# MSMGDustSensor.net
KiCad netlist of a schematic drawn in EAGLE
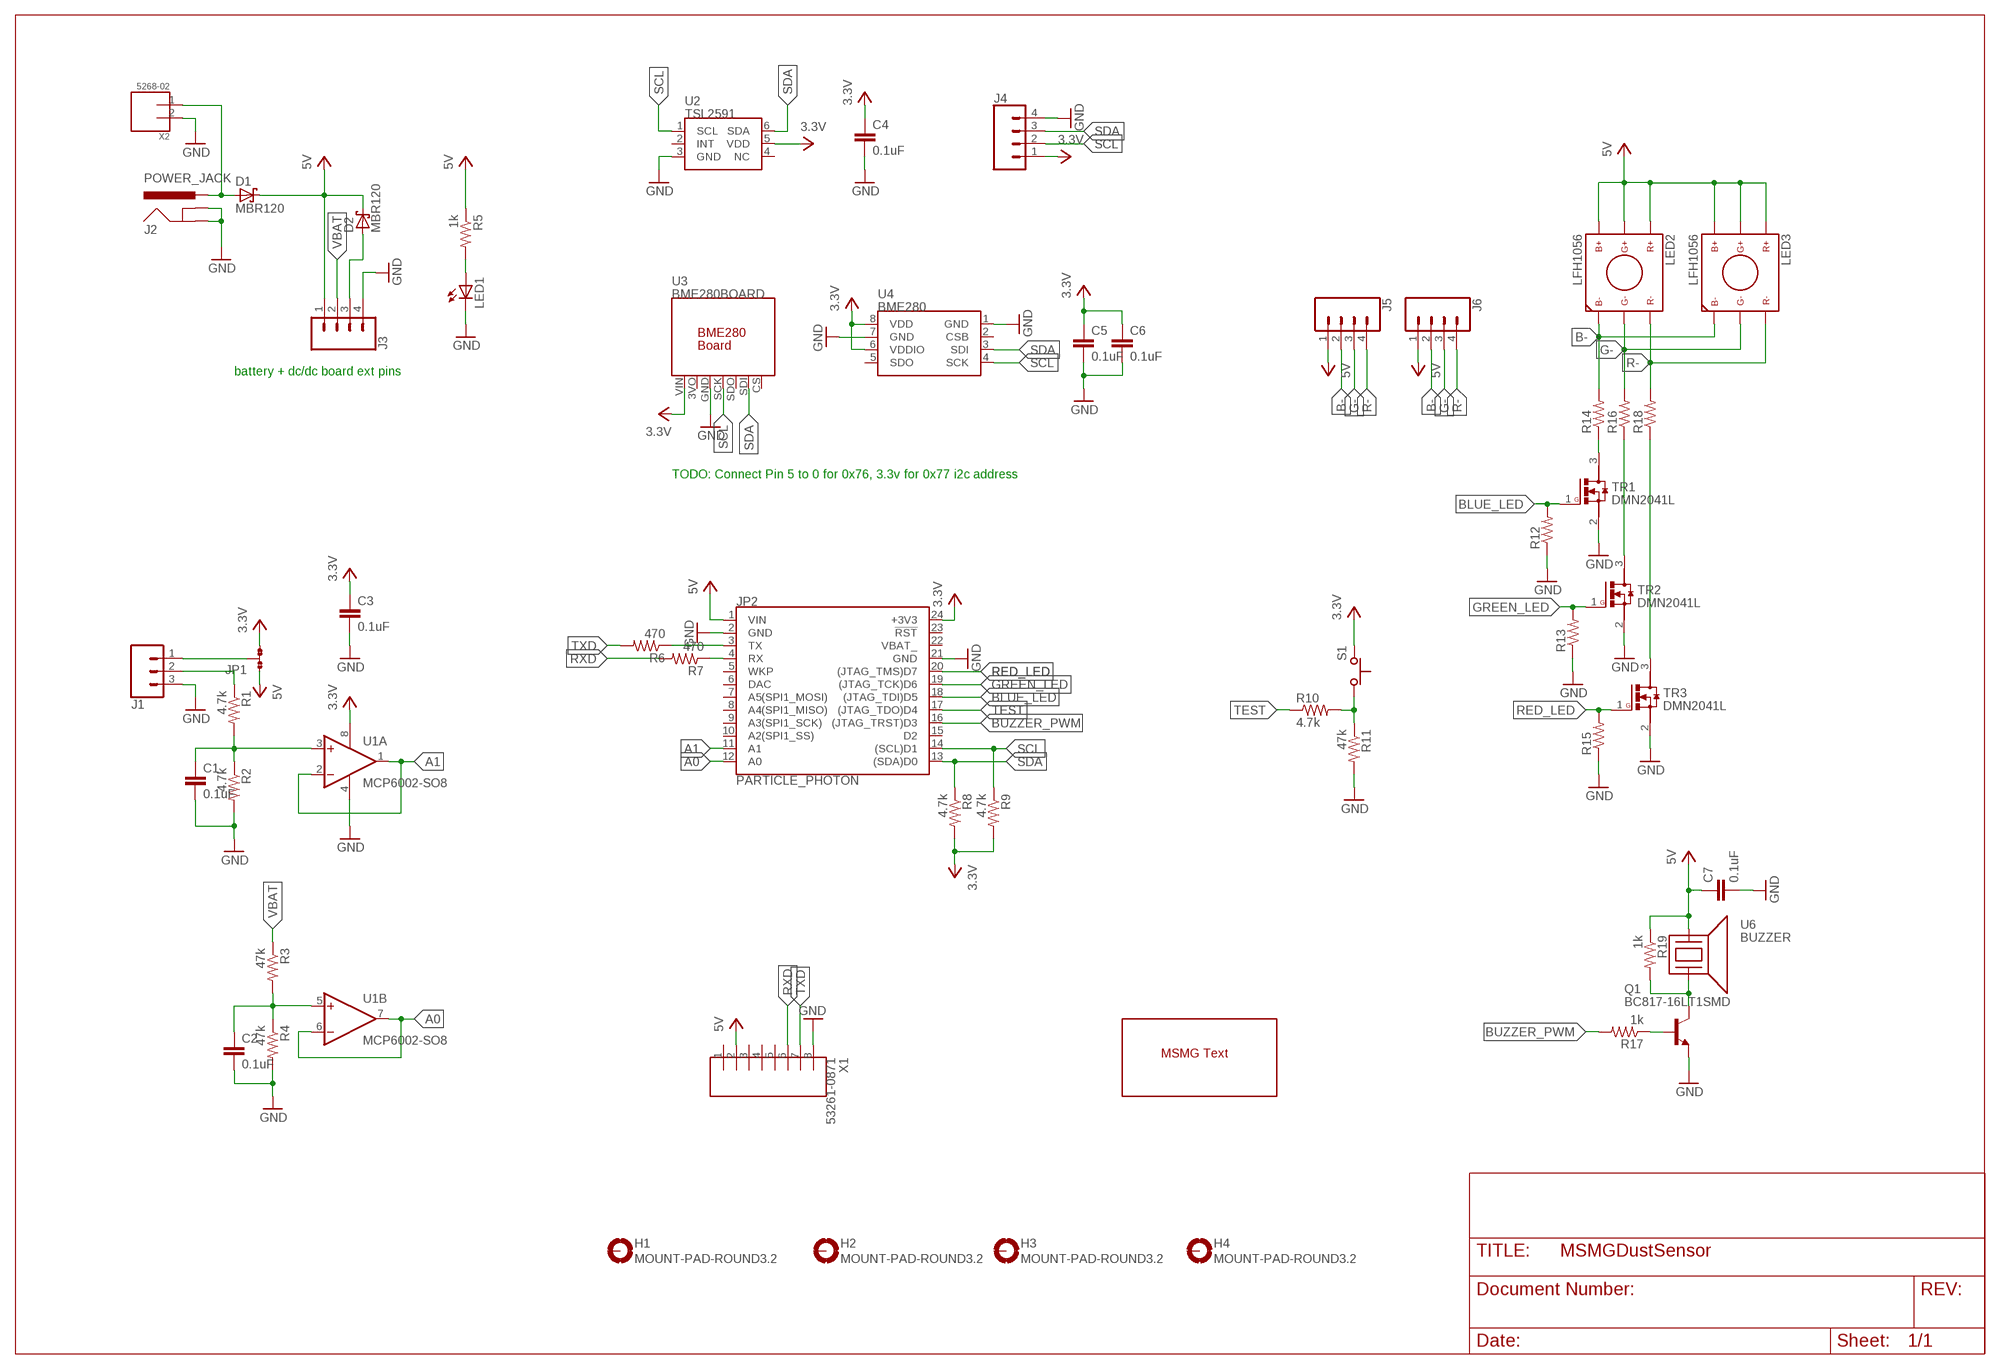
[diagram p0: schematic, sheet 1]

(export (version "E")
  (design (tool "Eeschema 10.0.6"))
  (components
    (comp (ref "C1")
      (value "0.1uF")
      (footprint "eagle-import:C0603(1608)")
      (libsource (lib "eagle-import") (part "C0603(1608)"))
    )
    (comp (ref "C2")
      (value "0.1uF")
      (footprint "eagle-import:C0603(1608)")
      (libsource (lib "eagle-import") (part "C0603(1608)"))
    )
    (comp (ref "C3")
      (value "0.1uF")
      (footprint "eagle-import:C0603(1608)")
      (libsource (lib "eagle-import") (part "C0603(1608)"))
    )
    (comp (ref "C4")
      (value "0.1uF")
      (footprint "eagle-import:C0603(1608)")
      (libsource (lib "eagle-import") (part "C0603(1608)"))
    )
    (comp (ref "C5")
      (value "0.1uF")
      (footprint "eagle-import:C0603(1608)")
      (libsource (lib "eagle-import") (part "C0603(1608)"))
    )
    (comp (ref "C6")
      (value "0.1uF")
      (footprint "eagle-import:C0603(1608)")
      (libsource (lib "eagle-import") (part "C0603(1608)"))
    )
    (comp (ref "C7")
      (value "0.1uF")
      (footprint "eagle-import:C0603(1608)")
      (libsource (lib "eagle-import") (part "C0603(1608)"))
    )
    (comp (ref "D1")
      (value "MBR120")
      (footprint "eagle-import:SOD-123")
      (libsource (lib "eagle-import") (part "MBR120"))
    )
    (comp (ref "D2")
      (value "MBR120")
      (footprint "eagle-import:SOD-123")
      (libsource (lib "eagle-import") (part "MBR120"))
    )
    (comp (ref "H1")
      (value "MOUNT-PAD-ROUND3.2")
      (footprint "eagle-import:3,2-PAD")
      (libsource (lib "eagle-import") (part "MOUNT-PAD-ROUND3.2"))
    )
    (comp (ref "H2")
      (value "MOUNT-PAD-ROUND3.2")
      (footprint "eagle-import:3,2-PAD")
      (libsource (lib "eagle-import") (part "MOUNT-PAD-ROUND3.2"))
    )
    (comp (ref "H3")
      (value "MOUNT-PAD-ROUND3.2")
      (footprint "eagle-import:3,2-PAD")
      (libsource (lib "eagle-import") (part "MOUNT-PAD-ROUND3.2"))
    )
    (comp (ref "H4")
      (value "MOUNT-PAD-ROUND3.2")
      (footprint "eagle-import:3,2-PAD")
      (libsource (lib "eagle-import") (part "MOUNT-PAD-ROUND3.2"))
    )
    (comp (ref "J1")
      (value "CONN_03")
      (footprint "eagle-import:1X03")
      (libsource (lib "eagle-import") (part "CONN_03"))
    )
    (comp (ref "J2")
      (value "POWER_JACK")
      (footprint "eagle-import:POWER_JACK_PTH")
      (libsource (lib "eagle-import") (part "POWER_JACK"))
    )
    (comp (ref "J3")
      (value "CONN_04")
      (footprint "eagle-import:1X04")
      (libsource (lib "eagle-import") (part "CONN_04"))
    )
    (comp (ref "J4")
      (value "CONN_04")
      (footprint "eagle-import:1X04")
      (libsource (lib "eagle-import") (part "CONN_04"))
    )
    (comp (ref "J5")
      (value "CONN_04")
      (footprint "eagle-import:1X04")
      (libsource (lib "eagle-import") (part "CONN_04"))
    )
    (comp (ref "J6")
      (value "CONN_04")
      (footprint "eagle-import:1X04")
      (libsource (lib "eagle-import") (part "CONN_04"))
    )
    (comp (ref "JP1")
      (value "JP2")
      (footprint "eagle-import:JP2SMD0603")
      (libsource (lib "eagle-import") (part "JP2"))
    )
    (comp (ref "JP2")
      (value "PARTICLE_PHOTON")
      (footprint "eagle-import:PARTICLE_PHOTON")
      (libsource (lib "eagle-import") (part "PARTICLE_PHOTON"))
    )
    (comp (ref "LED1")
      (value "LED3MM")
      (footprint "eagle-import:LED3MM")
      (libsource (lib "eagle-import") (part "LED3MM"))
    )
    (comp (ref "LED2")
      (value "LFH1056")
      (footprint "eagle-import:LFH1056")
      (libsource (lib "eagle-import") (part "LFH1056"))
    )
    (comp (ref "LED3")
      (value "LFH1056")
      (footprint "eagle-import:LFH1056")
      (libsource (lib "eagle-import") (part "LFH1056"))
    )
    (comp (ref "Q1")
      (value "BC817-16LT1SMD")
      (footprint "eagle-import:SOT23-BEC")
      (libsource (lib "eagle-import") (part "BC817SMD-16LT1"))
    )
    (comp (ref "R1")
      (value "4.7k")
      (footprint "eagle-import:R0603(1608)")
      (libsource (lib "eagle-import") (part "R0603(1608)"))
    )
    (comp (ref "R2")
      (value "4.7k")
      (footprint "eagle-import:R0603(1608)")
      (libsource (lib "eagle-import") (part "R0603(1608)"))
    )
    (comp (ref "R3")
      (value "47k")
      (footprint "eagle-import:R0603(1608)")
      (libsource (lib "eagle-import") (part "R0603(1608)"))
    )
    (comp (ref "R4")
      (value "47k")
      (footprint "eagle-import:R0603(1608)")
      (libsource (lib "eagle-import") (part "R0603(1608)"))
    )
    (comp (ref "R5")
      (value "1k")
      (footprint "eagle-import:R0603(1608)")
      (libsource (lib "eagle-import") (part "R0603(1608)"))
    )
    (comp (ref "R6")
      (value "470")
      (footprint "eagle-import:R0603(1608)")
      (libsource (lib "eagle-import") (part "R0603(1608)"))
    )
    (comp (ref "R7")
      (value "470")
      (footprint "eagle-import:R0603(1608)")
      (libsource (lib "eagle-import") (part "R0603(1608)"))
    )
    (comp (ref "R8")
      (value "4.7k")
      (footprint "eagle-import:R0603(1608)")
      (libsource (lib "eagle-import") (part "R0603(1608)"))
    )
    (comp (ref "R9")
      (value "4.7k")
      (footprint "eagle-import:R0603(1608)")
      (libsource (lib "eagle-import") (part "R0603(1608)"))
    )
    (comp (ref "R10")
      (value "4.7k")
      (footprint "eagle-import:R0603(1608)")
      (libsource (lib "eagle-import") (part "R0603(1608)"))
    )
    (comp (ref "R11")
      (value "47k")
      (footprint "eagle-import:R0603(1608)")
      (libsource (lib "eagle-import") (part "R0603(1608)"))
    )
    (comp (ref "R12")
      (value "R0603(1608)")
      (footprint "eagle-import:R0603(1608)")
      (libsource (lib "eagle-import") (part "R0603(1608)"))
    )
    (comp (ref "R13")
      (value "R0603(1608)")
      (footprint "eagle-import:R0603(1608)")
      (libsource (lib "eagle-import") (part "R0603(1608)"))
    )
    (comp (ref "R14")
      (value "R0603(1608)")
      (footprint "eagle-import:R0603(1608)")
      (libsource (lib "eagle-import") (part "R0603(1608)"))
    )
    (comp (ref "R15")
      (value "R0603(1608)")
      (footprint "eagle-import:R0603(1608)")
      (libsource (lib "eagle-import") (part "R0603(1608)"))
    )
    (comp (ref "R16")
      (value "R0603(1608)")
      (footprint "eagle-import:R0603(1608)")
      (libsource (lib "eagle-import") (part "R0603(1608)"))
    )
    (comp (ref "R17")
      (value "1k")
      (footprint "eagle-import:R0603(1608)")
      (libsource (lib "eagle-import") (part "R0603(1608)"))
    )
    (comp (ref "R18")
      (value "R0603(1608)")
      (footprint "eagle-import:R0603(1608)")
      (libsource (lib "eagle-import") (part "R0603(1608)"))
    )
    (comp (ref "R19")
      (value "1k")
      (footprint "eagle-import:R0603(1608)")
      (libsource (lib "eagle-import") (part "R0603(1608)"))
    )
    (comp (ref "S1")
      (value "SWITCH")
      (footprint "eagle-import:SKHLACA010")
      (libsource (lib "eagle-import") (part "SWITCH"))
    )
    (comp (ref "TR1")
      (value "DMN2041L")
      (footprint "eagle-import:SOT23")
      (libsource (lib "eagle-import") (part "DMN2041L"))
    )
    (comp (ref "TR2")
      (value "DMN2041L")
      (footprint "eagle-import:SOT23")
      (libsource (lib "eagle-import") (part "DMN2041L"))
    )
    (comp (ref "TR3")
      (value "DMN2041L")
      (footprint "eagle-import:SOT23")
      (libsource (lib "eagle-import") (part "DMN2041L"))
    )
    (comp (ref "U$1")
      (value "MSMG_TEXT")
      (footprint "eagle-import:MSMG_TEXT")
      (libsource (lib "eagle-import") (part "MSMG_TEXT"))
    )
    (comp (ref "U1")
      (value "MCP6002-SO8")
      (footprint "eagle-import:SO8")
      (libsource (lib "eagle-import") (part "MCP6002-SO8"))
    )
    (comp (ref "U2")
      (value "TSL2591")
      (footprint "eagle-import:DFN-6")
      (libsource (lib "eagle-import") (part "TSL2591"))
    )
    (comp (ref "U3")
      (value "BME280BOARD")
      (footprint "eagle-import:BME280BOARD")
      (libsource (lib "eagle-import") (part "BME280BOARD"))
    )
    (comp (ref "U4")
      (value "BME280")
      (footprint "eagle-import:BME280")
      (libsource (lib "eagle-import") (part "BME280"))
    )
    (comp (ref "U6")
      (value "BUZZER")
      (footprint "eagle-import:PS1240")
      (libsource (lib "eagle-import") (part "BUZZER"))
    )
    (comp (ref "X1")
      (value "53261-0871")
      (footprint "eagle-import:53261-0871")
      (libsource (lib "eagle-import") (part "53261-0871"))
    )
    (comp (ref "X2")
      (value "5268-02")
      (footprint "eagle-import:5628-02")
      (libsource (lib "eagle-import") (part "5268-02"))
    )
  )
  (nets
    (net (code "1") (name "/VBAT_") (class "Default")
      (node (ref "JP2") (pin "22") (pinfunction "VBAT__22") (pintype "power_in"))
    )
    (net (code "2") (name "3.3V") (class "Default")
      (node (ref "C3") (pin "1") (pinfunction "1_1") (pintype "passive"))
      (node (ref "C4") (pin "1") (pinfunction "1_1") (pintype "passive"))
      (node (ref "C5") (pin "1") (pinfunction "1_1") (pintype "passive"))
      (node (ref "C6") (pin "1") (pinfunction "1_1") (pintype "passive"))
      (node (ref "J4") (pin "1") (pinfunction "1_1") (pintype "passive"))
      (node (ref "JP1") (pin "3") (pinfunction "3_3") (pintype "passive"))
      (node (ref "JP2") (pin "24") (pinfunction "+3V3_24") (pintype "power_in"))
      (node (ref "R8") (pin "2") (pinfunction "2_2") (pintype "passive"))
      (node (ref "R9") (pin "2") (pinfunction "2_2") (pintype "passive"))
      (node (ref "S1") (pin "P$1") (pinfunction "P$1_P$1") (pintype "bidirectional"))
      (node (ref "U1") (pin "8") (pinfunction "V+_8") (pintype "power_in"))
      (node (ref "U2") (pin "5") (pinfunction "VDD_5") (pintype "bidirectional"))
      (node (ref "U3") (pin "VIN") (pinfunction "VIN_VIN") (pintype "bidirectional"))
      (node (ref "U4") (pin "6") (pinfunction "VDDIO_6") (pintype "power_in"))
      (node (ref "U4") (pin "8") (pinfunction "VDD_8") (pintype "power_in"))
    )
    (net (code "3") (name "5V") (class "Default")
      (node (ref "C7") (pin "1") (pinfunction "1_1") (pintype "passive"))
      (node (ref "D1") (pin "C") (pinfunction "C_C") (pintype "passive"))
      (node (ref "D2") (pin "C") (pinfunction "C_C") (pintype "passive"))
      (node (ref "J3") (pin "1") (pinfunction "1_1") (pintype "passive"))
      (node (ref "J5") (pin "1") (pinfunction "1_1") (pintype "passive"))
      (node (ref "J6") (pin "1") (pinfunction "1_1") (pintype "passive"))
      (node (ref "JP1") (pin "1") (pinfunction "1_1") (pintype "passive"))
      (node (ref "JP2") (pin "1") (pinfunction "VIN_1") (pintype "power_in"))
      (node (ref "LED2") (pin "B+") (pinfunction "B+_B+") (pintype "input"))
      (node (ref "LED2") (pin "G+") (pinfunction "G+_G+") (pintype "input"))
      (node (ref "LED2") (pin "R+") (pinfunction "R+_R+") (pintype "input"))
      (node (ref "LED3") (pin "B+") (pinfunction "B+_B+") (pintype "input"))
      (node (ref "LED3") (pin "G+") (pinfunction "G+_G+") (pintype "input"))
      (node (ref "LED3") (pin "R+") (pinfunction "R+_R+") (pintype "input"))
      (node (ref "R19") (pin "1") (pinfunction "1_1") (pintype "passive"))
      (node (ref "R5") (pin "1") (pinfunction "1_1") (pintype "passive"))
      (node (ref "U6") (pin "1") (pinfunction "P$1_1") (pintype "bidirectional"))
      (node (ref "X1") (pin "2") (pinfunction "2_2") (pintype "bidirectional"))
    )
    (net (code "4") (name "A0") (class "Default")
      (node (ref "JP2") (pin "12") (pinfunction "A0_12") (pintype "bidirectional"))
      (node (ref "U1") (pin "6") (pinfunction "-IN_6") (pintype "input"))
      (node (ref "U1") (pin "7") (pinfunction "OUT_7") (pintype "output"))
    )
    (net (code "5") (name "A1") (class "Default")
      (node (ref "JP2") (pin "11") (pinfunction "A1_11") (pintype "bidirectional"))
      (node (ref "U1") (pin "1") (pinfunction "OUT_1") (pintype "output"))
      (node (ref "U1") (pin "2") (pinfunction "-IN_2") (pintype "input"))
    )
    (net (code "6") (name "B-") (class "Default")
      (node (ref "J5") (pin "2") (pinfunction "2_2") (pintype "passive"))
      (node (ref "J6") (pin "2") (pinfunction "2_2") (pintype "passive"))
      (node (ref "LED2") (pin "B-") (pinfunction "B-_B-") (pintype "input"))
      (node (ref "LED3") (pin "B-") (pinfunction "B-_B-") (pintype "input"))
      (node (ref "R14") (pin "2") (pinfunction "2_2") (pintype "passive"))
    )
    (net (code "7") (name "BLUE_LED") (class "Default")
      (node (ref "JP2") (pin "18") (pinfunction "(JTAG_TDI)D5_18") (pintype "bidirectional"))
      (node (ref "R12") (pin "2") (pinfunction "2_2") (pintype "passive"))
      (node (ref "TR1") (pin "1") (pinfunction "G_1") (pintype "bidirectional"))
    )
    (net (code "8") (name "BUZZER_PWM") (class "Default")
      (node (ref "JP2") (pin "16") (pinfunction "(JTAG_TRST)D3_16") (pintype "bidirectional"))
      (node (ref "R17") (pin "2") (pinfunction "2_2") (pintype "passive"))
    )
    (net (code "9") (name "G-") (class "Default")
      (node (ref "J5") (pin "3") (pinfunction "3_3") (pintype "passive"))
      (node (ref "J6") (pin "3") (pinfunction "3_3") (pintype "passive"))
      (node (ref "LED2") (pin "G-") (pinfunction "G-_G-") (pintype "input"))
      (node (ref "LED3") (pin "G-") (pinfunction "G-_G-") (pintype "input"))
      (node (ref "R16") (pin "2") (pinfunction "2_2") (pintype "passive"))
    )
    (net (code "10") (name "GND") (class "Default")
      (node (ref "C1") (pin "2") (pinfunction "2_2") (pintype "passive"))
      (node (ref "C2") (pin "2") (pinfunction "2_2") (pintype "passive"))
      (node (ref "C3") (pin "2") (pinfunction "2_2") (pintype "passive"))
      (node (ref "C4") (pin "2") (pinfunction "2_2") (pintype "passive"))
      (node (ref "C5") (pin "2") (pinfunction "2_2") (pintype "passive"))
      (node (ref "C6") (pin "2") (pinfunction "2_2") (pintype "passive"))
      (node (ref "C7") (pin "2") (pinfunction "2_2") (pintype "passive"))
      (node (ref "J1") (pin "3") (pinfunction "3_3") (pintype "passive"))
      (node (ref "J2") (pin "GND") (pinfunction "GND_GND") (pintype "bidirectional"))
      (node (ref "J2") (pin "GNDBREAK") (pinfunction "GNDBREAK_GNDBREAK") (pintype "bidirectional"))
      (node (ref "J3") (pin "4") (pinfunction "4_4") (pintype "passive"))
      (node (ref "J4") (pin "4") (pinfunction "4_4") (pintype "passive"))
      (node (ref "JP2") (pin "2") (pinfunction "GND_2") (pintype "power_in"))
      (node (ref "JP2") (pin "21") (pinfunction "GND_21") (pintype "power_in"))
      (node (ref "LED1") (pin "K") (pinfunction "C_K") (pintype "passive"))
      (node (ref "Q1") (pin "E") (pinfunction "E_E") (pintype "passive"))
      (node (ref "R11") (pin "2") (pinfunction "2_2") (pintype "passive"))
      (node (ref "R12") (pin "1") (pinfunction "1_1") (pintype "passive"))
      (node (ref "R13") (pin "1") (pinfunction "1_1") (pintype "passive"))
      (node (ref "R15") (pin "1") (pinfunction "1_1") (pintype "passive"))
      (node (ref "R2") (pin "2") (pinfunction "2_2") (pintype "passive"))
      (node (ref "R4") (pin "2") (pinfunction "2_2") (pintype "passive"))
      (node (ref "TR1") (pin "2") (pinfunction "S_2") (pintype "bidirectional"))
      (node (ref "TR2") (pin "2") (pinfunction "S_2") (pintype "bidirectional"))
      (node (ref "TR3") (pin "2") (pinfunction "S_2") (pintype "bidirectional"))
      (node (ref "U1") (pin "4") (pinfunction "V-_4") (pintype "power_in"))
      (node (ref "U2") (pin "3") (pinfunction "GND_3") (pintype "bidirectional"))
      (node (ref "U3") (pin "GND") (pinfunction "GND_GND") (pintype "bidirectional"))
      (node (ref "U4") (pin "1") (pinfunction "GND_1") (pintype "power_in"))
      (node (ref "U4") (pin "7") (pinfunction "GND_7") (pintype "power_in"))
      (node (ref "X1") (pin "8") (pinfunction "8_8") (pintype "bidirectional"))
      (node (ref "X2") (pin "2") (pinfunction "2_2") (pintype "bidirectional"))
    )
    (net (code "11") (name "GREEN_LED") (class "Default")
      (node (ref "JP2") (pin "19") (pinfunction "(JTAG_TCK)D6_19") (pintype "bidirectional"))
      (node (ref "R13") (pin "2") (pinfunction "2_2") (pintype "passive"))
      (node (ref "TR2") (pin "1") (pinfunction "G_1") (pintype "bidirectional"))
    )
    (net (code "12") (name "Net-(D1-PadA)") (class "Default")
      (node (ref "D1") (pin "A") (pinfunction "A_A") (pintype "passive"))
      (node (ref "J2") (pin "PWR") (pinfunction "PWR_PWR") (pintype "bidirectional"))
      (node (ref "X2") (pin "1") (pinfunction "1_1") (pintype "bidirectional"))
    )
    (net (code "13") (name "Net-(D2-PadA)") (class "Default")
      (node (ref "D2") (pin "A") (pinfunction "A_A") (pintype "passive"))
      (node (ref "J3") (pin "3") (pinfunction "3_3") (pintype "passive"))
    )
    (net (code "14") (name "Net-(J1-Pad1)") (class "Default")
      (node (ref "J1") (pin "1") (pinfunction "1_1") (pintype "passive"))
      (node (ref "JP1") (pin "2") (pinfunction "2_2") (pintype "passive"))
    )
    (net (code "15") (name "Net-(J1-Pad2)") (class "Default")
      (node (ref "J1") (pin "2") (pinfunction "2_2") (pintype "passive"))
      (node (ref "R1") (pin "1") (pinfunction "1_1") (pintype "passive"))
    )
    (net (code "16") (name "Net-(JP2-RX)") (class "Default")
      (node (ref "JP2") (pin "4") (pinfunction "RX_4") (pintype "bidirectional"))
      (node (ref "R7") (pin "1") (pinfunction "1_1") (pintype "passive"))
    )
    (net (code "17") (name "Net-(JP2-TX)") (class "Default")
      (node (ref "JP2") (pin "3") (pinfunction "TX_3") (pintype "bidirectional"))
      (node (ref "R6") (pin "1") (pinfunction "1_1") (pintype "passive"))
    )
    (net (code "18") (name "Net-(LED1-PadA)") (class "Default")
      (node (ref "LED1") (pin "A") (pinfunction "A_A") (pintype "passive"))
      (node (ref "R5") (pin "2") (pinfunction "2_2") (pintype "passive"))
    )
    (net (code "19") (name "Net-(Q1-PadB)") (class "Default")
      (node (ref "Q1") (pin "B") (pinfunction "B_B") (pintype "passive"))
      (node (ref "R17") (pin "1") (pinfunction "1_1") (pintype "passive"))
    )
    (net (code "20") (name "Net-(R10-Pad2)") (class "Default")
      (node (ref "R10") (pin "2") (pinfunction "2_2") (pintype "passive"))
      (node (ref "R11") (pin "1") (pinfunction "1_1") (pintype "passive"))
      (node (ref "S1") (pin "P$2") (pinfunction "P$2_P$2") (pintype "bidirectional"))
    )
    (net (code "21") (name "Net-(TR1-D)") (class "Default")
      (node (ref "R14") (pin "1") (pinfunction "1_1") (pintype "passive"))
      (node (ref "TR1") (pin "3") (pinfunction "D_3") (pintype "bidirectional"))
    )
    (net (code "22") (name "Net-(TR2-D)") (class "Default")
      (node (ref "R16") (pin "1") (pinfunction "1_1") (pintype "passive"))
      (node (ref "TR2") (pin "3") (pinfunction "D_3") (pintype "bidirectional"))
    )
    (net (code "23") (name "Net-(TR3-D)") (class "Default")
      (node (ref "R18") (pin "1") (pinfunction "1_1") (pintype "passive"))
      (node (ref "TR3") (pin "3") (pinfunction "D_3") (pintype "bidirectional"))
    )
    (net (code "24") (name "Net-(U1A-+IN)") (class "Default")
      (node (ref "C1") (pin "1") (pinfunction "1_1") (pintype "passive"))
      (node (ref "R1") (pin "2") (pinfunction "2_2") (pintype "passive"))
      (node (ref "R2") (pin "1") (pinfunction "1_1") (pintype "passive"))
      (node (ref "U1") (pin "3") (pinfunction "+IN_3") (pintype "input"))
    )
    (net (code "25") (name "Net-(U1B-+IN)") (class "Default")
      (node (ref "C2") (pin "1") (pinfunction "1_1") (pintype "passive"))
      (node (ref "R3") (pin "2") (pinfunction "2_2") (pintype "passive"))
      (node (ref "R4") (pin "1") (pinfunction "1_1") (pintype "passive"))
      (node (ref "U1") (pin "5") (pinfunction "+IN_5") (pintype "input"))
    )
    (net (code "26") (name "Net-(U6-P$2)") (class "Default")
      (node (ref "Q1") (pin "C") (pinfunction "C_C") (pintype "passive"))
      (node (ref "R19") (pin "2") (pinfunction "2_2") (pintype "passive"))
      (node (ref "U6") (pin "2") (pinfunction "P$2_2") (pintype "bidirectional"))
    )
    (net (code "27") (name "R-") (class "Default")
      (node (ref "J5") (pin "4") (pinfunction "4_4") (pintype "passive"))
      (node (ref "J6") (pin "4") (pinfunction "4_4") (pintype "passive"))
      (node (ref "LED2") (pin "R-") (pinfunction "R-_R-") (pintype "input"))
      (node (ref "LED3") (pin "R-") (pinfunction "R-_R-") (pintype "input"))
      (node (ref "R18") (pin "2") (pinfunction "2_2") (pintype "passive"))
    )
    (net (code "28") (name "RED_LED") (class "Default")
      (node (ref "JP2") (pin "20") (pinfunction "(JTAG_TMS)D7_20") (pintype "bidirectional"))
      (node (ref "R15") (pin "2") (pinfunction "2_2") (pintype "passive"))
      (node (ref "TR3") (pin "1") (pinfunction "G_1") (pintype "bidirectional"))
    )
    (net (code "29") (name "RXD") (class "Default")
      (node (ref "R7") (pin "2") (pinfunction "2_2") (pintype "passive"))
      (node (ref "X1") (pin "6") (pinfunction "6_6") (pintype "bidirectional"))
    )
    (net (code "30") (name "SCL") (class "Default")
      (node (ref "J4") (pin "2") (pinfunction "2_2") (pintype "passive"))
      (node (ref "JP2") (pin "14") (pinfunction "(SCL)D1_14") (pintype "bidirectional"))
      (node (ref "R9") (pin "1") (pinfunction "1_1") (pintype "passive"))
      (node (ref "U2") (pin "1") (pinfunction "SCL_1") (pintype "bidirectional"))
      (node (ref "U3") (pin "SCK") (pinfunction "SCK_SCK") (pintype "bidirectional"))
      (node (ref "U4") (pin "4") (pinfunction "SCK_4") (pintype "input"))
    )
    (net (code "31") (name "SDA") (class "Default")
      (node (ref "J4") (pin "3") (pinfunction "3_3") (pintype "passive"))
      (node (ref "JP2") (pin "13") (pinfunction "(SDA)D0_13") (pintype "bidirectional"))
      (node (ref "R8") (pin "1") (pinfunction "1_1") (pintype "passive"))
      (node (ref "U2") (pin "6") (pinfunction "SDA_6") (pintype "bidirectional"))
      (node (ref "U3") (pin "SDI") (pinfunction "SDI_SDI") (pintype "bidirectional"))
      (node (ref "U4") (pin "3") (pinfunction "SDI_3") (pintype "input"))
    )
    (net (code "32") (name "TEST") (class "Default")
      (node (ref "JP2") (pin "17") (pinfunction "(JTAG_TDO)D4_17") (pintype "bidirectional"))
      (node (ref "R10") (pin "1") (pinfunction "1_1") (pintype "passive"))
    )
    (net (code "33") (name "TXD") (class "Default")
      (node (ref "R6") (pin "2") (pinfunction "2_2") (pintype "passive"))
      (node (ref "X1") (pin "7") (pinfunction "7_7") (pintype "bidirectional"))
    )
    (net (code "34") (name "VBAT") (class "Default")
      (node (ref "J3") (pin "2") (pinfunction "2_2") (pintype "passive"))
      (node (ref "R3") (pin "1") (pinfunction "1_1") (pintype "passive"))
    )
    (net (code "35") (name "unconnected-(H1-MOUNT-PadB3,2)") (class "Default")
      (node (ref "H1") (pin "B3,2") (pinfunction "MOUNT_B3,2") (pintype "passive"))
    )
    (net (code "36") (name "unconnected-(H2-MOUNT-PadB3,2)") (class "Default")
      (node (ref "H2") (pin "B3,2") (pinfunction "MOUNT_B3,2") (pintype "passive"))
    )
    (net (code "37") (name "unconnected-(H3-MOUNT-PadB3,2)") (class "Default")
      (node (ref "H3") (pin "B3,2") (pinfunction "MOUNT_B3,2") (pintype "passive"))
    )
    (net (code "38") (name "unconnected-(H4-MOUNT-PadB3,2)") (class "Default")
      (node (ref "H4") (pin "B3,2") (pinfunction "MOUNT_B3,2") (pintype "passive"))
    )
    (net (code "39") (name "unconnected-(JP2-A2(SPI1_SS)-Pad10)") (class "Default")
      (node (ref "JP2") (pin "10") (pinfunction "A2(SPI1_SS)_10") (pintype "bidirectional"))
    )
    (net (code "40") (name "unconnected-(JP2-A3(SPI1_SCK)-Pad9)") (class "Default")
      (node (ref "JP2") (pin "9") (pinfunction "A3(SPI1_SCK)_9") (pintype "bidirectional"))
    )
    (net (code "41") (name "unconnected-(JP2-A4(SPI1_MISO)-Pad8)") (class "Default")
      (node (ref "JP2") (pin "8") (pinfunction "A4(SPI1_MISO)_8") (pintype "bidirectional"))
    )
    (net (code "42") (name "unconnected-(JP2-A5(SPI1_MOSI)-Pad7)") (class "Default")
      (node (ref "JP2") (pin "7") (pinfunction "A5(SPI1_MOSI)_7") (pintype "bidirectional"))
    )
    (net (code "43") (name "unconnected-(JP2-D2-Pad15)") (class "Default")
      (node (ref "JP2") (pin "15") (pinfunction "D2_15") (pintype "bidirectional"))
    )
    (net (code "44") (name "unconnected-(JP2-DAC-Pad6)") (class "Default")
      (node (ref "JP2") (pin "6") (pinfunction "DAC_6") (pintype "bidirectional"))
    )
    (net (code "45") (name "unconnected-(JP2-WKP-Pad5)") (class "Default")
      (node (ref "JP2") (pin "5") (pinfunction "WKP_5") (pintype "bidirectional"))
    )
    (net (code "46") (name "unconnected-(JP2-~{RST}-Pad23)") (class "Default")
      (node (ref "JP2") (pin "23") (pinfunction "~{RST}_23") (pintype "bidirectional"))
    )
    (net (code "47") (name "unconnected-(U2-INT-Pad2)") (class "Default")
      (node (ref "U2") (pin "2") (pinfunction "INT_2") (pintype "bidirectional"))
    )
    (net (code "48") (name "unconnected-(U2-NC-Pad4)") (class "Default")
      (node (ref "U2") (pin "4") (pinfunction "NC_4") (pintype "bidirectional"))
    )
    (net (code "49") (name "unconnected-(U3-Pad3VO)") (class "Default")
      (node (ref "U3") (pin "3VO") (pinfunction "3VO_3VO") (pintype "bidirectional"))
    )
    (net (code "50") (name "unconnected-(U3-PadCS)") (class "Default")
      (node (ref "U3") (pin "CS") (pinfunction "CS_CS") (pintype "bidirectional"))
    )
    (net (code "51") (name "unconnected-(U3-PadSDO)") (class "Default")
      (node (ref "U3") (pin "SDO") (pinfunction "SDO_SDO") (pintype "bidirectional"))
    )
    (net (code "52") (name "unconnected-(U4-CSB-Pad2)") (class "Default")
      (node (ref "U4") (pin "2") (pinfunction "CSB_2") (pintype "input"))
    )
    (net (code "53") (name "unconnected-(U4-SDO-Pad5)") (class "Default")
      (node (ref "U4") (pin "5") (pinfunction "SDO_5") (pintype "output"))
    )
    (net (code "54") (name "unconnected-(X1-Pad1)") (class "Default")
      (node (ref "X1") (pin "1") (pinfunction "1_1") (pintype "bidirectional"))
    )
    (net (code "55") (name "unconnected-(X1-Pad3)") (class "Default")
      (node (ref "X1") (pin "3") (pinfunction "3_3") (pintype "bidirectional"))
    )
    (net (code "56") (name "unconnected-(X1-Pad4)") (class "Default")
      (node (ref "X1") (pin "4") (pinfunction "4_4") (pintype "bidirectional"))
    )
    (net (code "57") (name "unconnected-(X1-Pad5)") (class "Default")
      (node (ref "X1") (pin "5") (pinfunction "5_5") (pintype "bidirectional"))
    )
  )
)
